# Connectors.net
KiCad netlist of a schematic drawn in Altium Designer
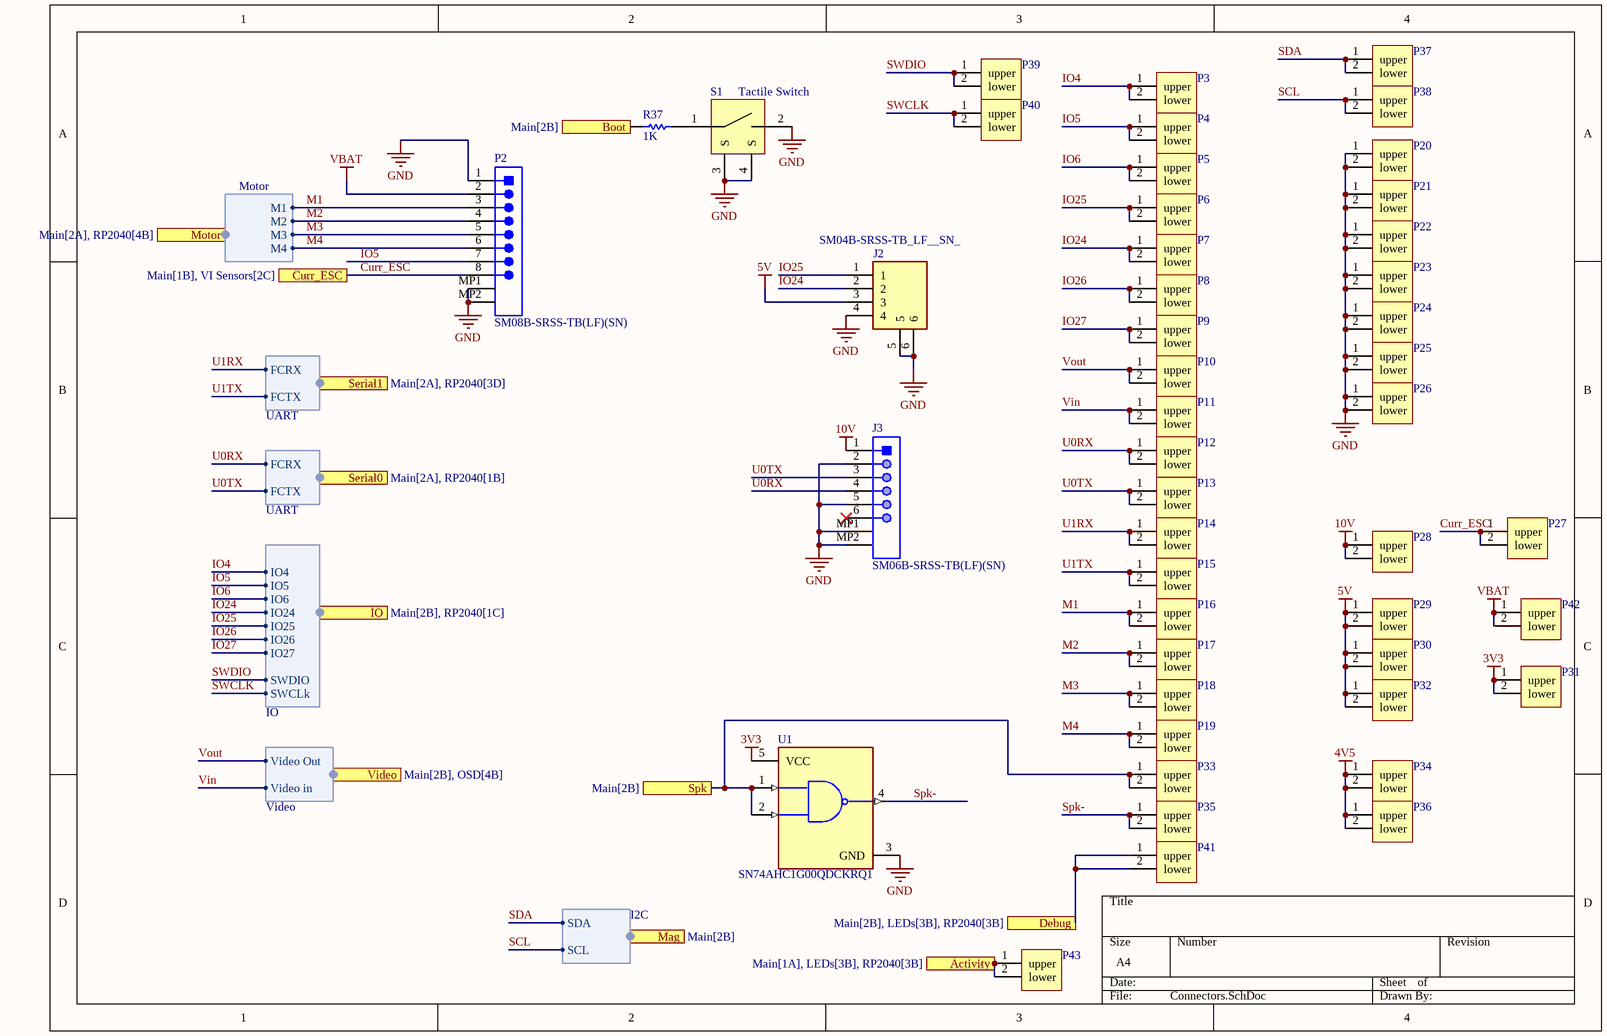
[diagram p0: Connectors.SchDoc]

(export (version "E")
  (design (tool "Eeschema 10.0.6"))
  (components
    (comp (ref "J2")
      (value "SM04B-SRSS-TB_LF__SN_")
      (footprint "SM04B-SRSS-TB(LFSN)")
      (description "Connector")
      (fields (field (name "MANUFACTURER_PART_NUMBER") "SM04B-SRSS-TB(LF)(SN)"))
      (libsource (lib "Custom Components") (part "SM04B-SRSS-TB_LF__SN_"))
    )
    (comp (ref "J3")
      (value "SM06B-SRSS-TB(LF)(SN)")
      (footprint "JST-SM06B-SRSS-TB_V")
      (description "Male Header, Pitch 1 mm, 1 x 6 Position, Height 2.95 mm, -25 to 85 degC, RoHS, Tape and Reel")
      (fields (field (name "MANUFACTURER") "JST"))
      (libsource (lib "Altium Content Vault") (part "CN-1P-2M-R6"))
    )
    (comp (ref "P2")
      (value "SM08B-SRSS-TB(LF)(SN)")
      (footprint "JST-SM08B-SRSS-TB_V")
      (description "Male Header, Pitch 1 mm, 1 x 8 Position, Height 2.95 mm, -25 to 85 degC, RoHS, Tape and Reel")
      (fields (field (name "MANUFACTURER") "JST"))
      (libsource (lib "Altium Content Vault") (part "CN-1P-2M-R8"))
    )
    (comp (ref "P3")
      (value "solder pad rounded double sided")
      (footprint "solder pad double sided rounded - duplicate")
      (libsource (lib "Custom Components") (part "solder pad rounded double sided"))
    )
    (comp (ref "P4")
      (value "solder pad rounded double sided")
      (footprint "solder pad double sided rounded - duplicate")
      (libsource (lib "Custom Components") (part "solder pad rounded double sided"))
    )
    (comp (ref "P5")
      (value "solder pad rounded double sided")
      (footprint "solder pad double sided rounded - duplicate")
      (libsource (lib "Custom Components") (part "solder pad rounded double sided"))
    )
    (comp (ref "P6")
      (value "solder pad rounded double sided")
      (footprint "solder pad double sided rounded - duplicate")
      (libsource (lib "Custom Components") (part "solder pad rounded double sided"))
    )
    (comp (ref "P7")
      (value "solder pad rounded double sided")
      (footprint "solder pad double sided rounded - duplicate")
      (libsource (lib "Custom Components") (part "solder pad rounded double sided"))
    )
    (comp (ref "P8")
      (value "solder pad rounded double sided")
      (footprint "solder pad double sided rounded - duplicate")
      (libsource (lib "Custom Components") (part "solder pad rounded double sided"))
    )
    (comp (ref "P9")
      (value "solder pad rounded double sided")
      (footprint "solder pad double sided rounded - duplicate")
      (libsource (lib "Custom Components") (part "solder pad rounded double sided"))
    )
    (comp (ref "P10")
      (value "solder pad rounded double sided")
      (footprint "solder pad double sided rounded - duplicate")
      (libsource (lib "Custom Components") (part "solder pad rounded double sided"))
    )
    (comp (ref "P11")
      (value "solder pad rounded double sided")
      (footprint "solder pad double sided rounded - duplicate")
      (libsource (lib "Custom Components") (part "solder pad rounded double sided"))
    )
    (comp (ref "P12")
      (value "solder pad rounded double sided")
      (footprint "solder pad double sided rounded - duplicate")
      (libsource (lib "Custom Components") (part "solder pad rounded double sided"))
    )
    (comp (ref "P13")
      (value "solder pad rounded double sided")
      (footprint "solder pad double sided rounded - duplicate")
      (libsource (lib "Custom Components") (part "solder pad rounded double sided"))
    )
    (comp (ref "P14")
      (value "solder pad rounded double sided")
      (footprint "solder pad double sided rounded - duplicate")
      (libsource (lib "Custom Components") (part "solder pad rounded double sided"))
    )
    (comp (ref "P15")
      (value "solder pad rounded double sided")
      (footprint "solder pad double sided rounded - duplicate")
      (libsource (lib "Custom Components") (part "solder pad rounded double sided"))
    )
    (comp (ref "P16")
      (value "solder pad rounded double sided")
      (footprint "solder pad double sided rounded - duplicate")
      (libsource (lib "Custom Components") (part "solder pad rounded double sided"))
    )
    (comp (ref "P17")
      (value "solder pad rounded double sided")
      (footprint "solder pad double sided rounded - duplicate")
      (libsource (lib "Custom Components") (part "solder pad rounded double sided"))
    )
    (comp (ref "P18")
      (value "solder pad rounded double sided")
      (footprint "solder pad double sided rounded - duplicate")
      (libsource (lib "Custom Components") (part "solder pad rounded double sided"))
    )
    (comp (ref "P19")
      (value "solder pad rounded double sided")
      (footprint "solder pad double sided rounded - duplicate")
      (libsource (lib "Custom Components") (part "solder pad rounded double sided"))
    )
    (comp (ref "P20")
      (value "solder pad square double sided")
      (footprint "solder pad double sided square")
      (libsource (lib "Custom Components") (part "solder pad square double sided"))
    )
    (comp (ref "P21")
      (value "solder pad square double sided")
      (footprint "solder pad double sided square")
      (libsource (lib "Custom Components") (part "solder pad square double sided"))
    )
    (comp (ref "P22")
      (value "solder pad square double sided")
      (footprint "solder pad double sided square")
      (libsource (lib "Custom Components") (part "solder pad square double sided"))
    )
    (comp (ref "P23")
      (value "solder pad square double sided")
      (footprint "solder pad double sided square")
      (libsource (lib "Custom Components") (part "solder pad square double sided"))
    )
    (comp (ref "P24")
      (value "solder pad square double sided")
      (footprint "solder pad double sided square")
      (libsource (lib "Custom Components") (part "solder pad square double sided"))
    )
    (comp (ref "P25")
      (value "solder pad square double sided")
      (footprint "solder pad double sided square")
      (libsource (lib "Custom Components") (part "solder pad square double sided"))
    )
    (comp (ref "P26")
      (value "solder pad square double sided")
      (footprint "solder pad double sided square")
      (libsource (lib "Custom Components") (part "solder pad square double sided"))
    )
    (comp (ref "P27")
      (value "solder pad chamfered double sided")
      (footprint "solder pad double sided chamfered")
      (libsource (lib "Custom Components") (part "solder pad chamfered double sided"))
    )
    (comp (ref "P28")
      (value "solder pad chamfered double sided")
      (footprint "solder pad double sided chamfered")
      (libsource (lib "Custom Components") (part "solder pad chamfered double sided"))
    )
    (comp (ref "P29")
      (value "solder pad chamfered double sided")
      (footprint "solder pad double sided chamfered")
      (libsource (lib "Custom Components") (part "solder pad chamfered double sided"))
    )
    (comp (ref "P30")
      (value "solder pad chamfered double sided")
      (footprint "solder pad double sided chamfered")
      (libsource (lib "Custom Components") (part "solder pad chamfered double sided"))
    )
    (comp (ref "P31")
      (value "solder pad chamfered double sided")
      (footprint "solder pad double sided chamfered")
      (libsource (lib "Custom Components") (part "solder pad chamfered double sided"))
    )
    (comp (ref "P32")
      (value "solder pad chamfered double sided")
      (footprint "solder pad double sided chamfered")
      (libsource (lib "Custom Components") (part "solder pad chamfered double sided"))
    )
    (comp (ref "P33")
      (value "solder pad rounded double sided")
      (footprint "solder pad double sided rounded - duplicate")
      (libsource (lib "Custom Components") (part "solder pad rounded double sided"))
    )
    (comp (ref "P34")
      (value "solder pad chamfered double sided")
      (footprint "solder pad double sided chamfered")
      (libsource (lib "Custom Components") (part "solder pad chamfered double sided"))
    )
    (comp (ref "P35")
      (value "solder pad rounded double sided")
      (footprint "solder pad double sided rounded - duplicate")
      (libsource (lib "Custom Components") (part "solder pad rounded double sided"))
    )
    (comp (ref "P36")
      (value "solder pad chamfered double sided")
      (footprint "solder pad double sided chamfered")
      (libsource (lib "Custom Components") (part "solder pad chamfered double sided"))
    )
    (comp (ref "P37")
      (value "solder pad rounded double sided")
      (footprint "solder pad double sided rounded - duplicate")
      (libsource (lib "Custom Components") (part "solder pad rounded double sided"))
    )
    (comp (ref "P38")
      (value "solder pad rounded double sided")
      (footprint "solder pad double sided rounded - duplicate")
      (libsource (lib "Custom Components") (part "solder pad rounded double sided"))
    )
    (comp (ref "P39")
      (value "solder pad rounded double sided")
      (footprint "solder pad double sided rounded - duplicate")
      (libsource (lib "Custom Components") (part "solder pad rounded double sided"))
    )
    (comp (ref "P40")
      (value "solder pad rounded double sided")
      (footprint "solder pad double sided rounded - duplicate")
      (libsource (lib "Custom Components") (part "solder pad rounded double sided"))
    )
    (comp (ref "P41")
      (value "solder pad rounded double sided")
      (footprint "solder pad double sided rounded - duplicate")
      (libsource (lib "Custom Components") (part "solder pad rounded double sided"))
    )
    (comp (ref "P42")
      (value "solder pad chamfered double sided")
      (footprint "solder pad double sided chamfered")
      (libsource (lib "Custom Components") (part "solder pad chamfered double sided"))
    )
    (comp (ref "P43")
      (value "solder pad rounded double sided")
      (footprint "solder pad double sided rounded - duplicate")
      (libsource (lib "Custom Components") (part "solder pad rounded double sided"))
    )
    (comp (ref "R37")
      (value "1K")
      (footprint "RESC0603(1608)_N")
      (description "Chipwiderstand, SMD, Baureihe MC, 1%")
      (fields (field (name "MANUFACTURER") "Multicomp"))
      (libsource (lib "Standardbauteile") (part "Res 1K"))
    )
    (comp (ref "S1")
      (value "Tactile Switch")
      (footprint "Tactile Switch")
      (libsource (lib "Custom Components") (part "Tactile Switch"))
    )
    (comp (ref "U1")
      (value "SN74AHC1G00QDCKRQ1")
      (footprint "FP-DCK0005A-IPC_A")
      (description "IC GATE NAND 1CH 2-INP SC70-5")
      (libsource (lib "Altium Content Vault") (part "4a1d673274a90161e31fa41c5f74738"))
    )
  )
  (nets
    (net (code "6") (name "/Activity") (class "Default")
      (node (ref "P43") (pin "1") (pinfunction "upper_1") (pintype "passive"))
      (node (ref "P43") (pin "2") (pinfunction "lower_2") (pintype "passive"))
    )
    (net (code "7") (name "/Boot") (class "Default")
      (node (ref "R37") (pin "1") (pinfunction "1_1") (pintype "passive"))
    )
    (net (code "8") (name "/Curr_ESC") (class "Default")
      (node (ref "P2") (pin "8") (pinfunction "8_8") (pintype "passive"))
      (node (ref "P27") (pin "1") (pinfunction "upper_1") (pintype "passive"))
      (node (ref "P27") (pin "2") (pinfunction "lower_2") (pintype "passive"))
    )
    (net (code "9") (name "/Debug") (class "Default")
      (node (ref "P41") (pin "1") (pinfunction "upper_1") (pintype "passive"))
      (node (ref "P41") (pin "2") (pinfunction "lower_2") (pintype "passive"))
    )
    (net (code "10") (name "/IO4") (class "Default")
      (node (ref "P3") (pin "1") (pinfunction "upper_1") (pintype "passive"))
      (node (ref "P3") (pin "2") (pinfunction "lower_2") (pintype "passive"))
    )
    (net (code "11") (name "/IO5") (class "Default")
      (node (ref "P2") (pin "7") (pinfunction "7_7") (pintype "passive"))
      (node (ref "P4") (pin "1") (pinfunction "upper_1") (pintype "passive"))
      (node (ref "P4") (pin "2") (pinfunction "lower_2") (pintype "passive"))
    )
    (net (code "12") (name "/IO6") (class "Default")
      (node (ref "P5") (pin "1") (pinfunction "upper_1") (pintype "passive"))
      (node (ref "P5") (pin "2") (pinfunction "lower_2") (pintype "passive"))
    )
    (net (code "13") (name "/IO24") (class "Default")
      (node (ref "J2") (pin "2") (pinfunction "2_2") (pintype "passive"))
      (node (ref "P7") (pin "1") (pinfunction "upper_1") (pintype "passive"))
      (node (ref "P7") (pin "2") (pinfunction "lower_2") (pintype "passive"))
    )
    (net (code "14") (name "/IO25") (class "Default")
      (node (ref "J2") (pin "1") (pinfunction "1_1") (pintype "passive"))
      (node (ref "P6") (pin "1") (pinfunction "upper_1") (pintype "passive"))
      (node (ref "P6") (pin "2") (pinfunction "lower_2") (pintype "passive"))
    )
    (net (code "15") (name "/IO26") (class "Default")
      (node (ref "P8") (pin "1") (pinfunction "upper_1") (pintype "passive"))
      (node (ref "P8") (pin "2") (pinfunction "lower_2") (pintype "passive"))
    )
    (net (code "16") (name "/IO27") (class "Default")
      (node (ref "P9") (pin "1") (pinfunction "upper_1") (pintype "passive"))
      (node (ref "P9") (pin "2") (pinfunction "lower_2") (pintype "passive"))
    )
    (net (code "17") (name "/M1") (class "Default")
      (node (ref "P16") (pin "1") (pinfunction "upper_1") (pintype "passive"))
      (node (ref "P16") (pin "2") (pinfunction "lower_2") (pintype "passive"))
      (node (ref "P2") (pin "3") (pinfunction "3_3") (pintype "passive"))
    )
    (net (code "18") (name "/M2") (class "Default")
      (node (ref "P17") (pin "1") (pinfunction "upper_1") (pintype "passive"))
      (node (ref "P17") (pin "2") (pinfunction "lower_2") (pintype "passive"))
      (node (ref "P2") (pin "4") (pinfunction "4_4") (pintype "passive"))
    )
    (net (code "19") (name "/M3") (class "Default")
      (node (ref "P18") (pin "1") (pinfunction "upper_1") (pintype "passive"))
      (node (ref "P18") (pin "2") (pinfunction "lower_2") (pintype "passive"))
      (node (ref "P2") (pin "5") (pinfunction "5_5") (pintype "passive"))
    )
    (net (code "20") (name "/M4") (class "Default")
      (node (ref "P19") (pin "1") (pinfunction "upper_1") (pintype "passive"))
      (node (ref "P19") (pin "2") (pinfunction "lower_2") (pintype "passive"))
      (node (ref "P2") (pin "6") (pinfunction "6_6") (pintype "passive"))
    )
    (net (code "21") (name "/SCL") (class "Default")
      (node (ref "P38") (pin "1") (pinfunction "upper_1") (pintype "passive"))
      (node (ref "P38") (pin "2") (pinfunction "lower_2") (pintype "passive"))
    )
    (net (code "22") (name "/SDA") (class "Default")
      (node (ref "P37") (pin "1") (pinfunction "upper_1") (pintype "passive"))
      (node (ref "P37") (pin "2") (pinfunction "lower_2") (pintype "passive"))
    )
    (net (code "23") (name "/SWCLK") (class "Default")
      (node (ref "P40") (pin "1") (pinfunction "upper_1") (pintype "passive"))
      (node (ref "P40") (pin "2") (pinfunction "lower_2") (pintype "passive"))
    )
    (net (code "24") (name "/SWDIO") (class "Default")
      (node (ref "P39") (pin "1") (pinfunction "upper_1") (pintype "passive"))
      (node (ref "P39") (pin "2") (pinfunction "lower_2") (pintype "passive"))
    )
    (net (code "25") (name "/Spk") (class "Default")
      (node (ref "P33") (pin "1") (pinfunction "upper_1") (pintype "passive"))
      (node (ref "P33") (pin "2") (pinfunction "lower_2") (pintype "passive"))
      (node (ref "U1") (pin "1") (pinfunction "A_1") (pintype "input"))
      (node (ref "U1") (pin "2") (pinfunction "B_2") (pintype "input"))
    )
    (net (code "26") (name "/Spk-") (class "Default")
      (node (ref "P35") (pin "1") (pinfunction "upper_1") (pintype "passive"))
      (node (ref "P35") (pin "2") (pinfunction "lower_2") (pintype "passive"))
      (node (ref "U1") (pin "4") (pinfunction "Y_4") (pintype "output"))
    )
    (net (code "27") (name "/U0RX") (class "Default")
      (node (ref "J3") (pin "4") (pinfunction "4_4") (pintype "passive"))
      (node (ref "P12") (pin "1") (pinfunction "upper_1") (pintype "passive"))
      (node (ref "P12") (pin "2") (pinfunction "lower_2") (pintype "passive"))
    )
    (net (code "28") (name "/U0TX") (class "Default")
      (node (ref "J3") (pin "3") (pinfunction "3_3") (pintype "passive"))
      (node (ref "P13") (pin "1") (pinfunction "upper_1") (pintype "passive"))
      (node (ref "P13") (pin "2") (pinfunction "lower_2") (pintype "passive"))
    )
    (net (code "29") (name "/U1RX") (class "Default")
      (node (ref "P14") (pin "1") (pinfunction "upper_1") (pintype "passive"))
      (node (ref "P14") (pin "2") (pinfunction "lower_2") (pintype "passive"))
    )
    (net (code "30") (name "/U1TX") (class "Default")
      (node (ref "P15") (pin "1") (pinfunction "upper_1") (pintype "passive"))
      (node (ref "P15") (pin "2") (pinfunction "lower_2") (pintype "passive"))
    )
    (net (code "31") (name "/Vin") (class "Default")
      (node (ref "P11") (pin "1") (pinfunction "upper_1") (pintype "passive"))
      (node (ref "P11") (pin "2") (pinfunction "lower_2") (pintype "passive"))
    )
    (net (code "32") (name "/Vout") (class "Default")
      (node (ref "P10") (pin "1") (pinfunction "upper_1") (pintype "passive"))
      (node (ref "P10") (pin "2") (pinfunction "lower_2") (pintype "passive"))
    )
    (net (code "38") (name "3V3") (class "Default")
      (node (ref "P31") (pin "1") (pinfunction "upper_1") (pintype "passive"))
      (node (ref "P31") (pin "2") (pinfunction "lower_2") (pintype "passive"))
      (node (ref "U1") (pin "5") (pinfunction "VCC_5") (pintype "power_in"))
    )
    (net (code "39") (name "4V5") (class "Default")
      (node (ref "P34") (pin "1") (pinfunction "upper_1") (pintype "passive"))
      (node (ref "P34") (pin "2") (pinfunction "lower_2") (pintype "passive"))
      (node (ref "P36") (pin "1") (pinfunction "upper_1") (pintype "passive"))
      (node (ref "P36") (pin "2") (pinfunction "lower_2") (pintype "passive"))
    )
    (net (code "40") (name "5V") (class "Default")
      (node (ref "J2") (pin "3") (pinfunction "3_3") (pintype "passive"))
      (node (ref "P29") (pin "1") (pinfunction "upper_1") (pintype "passive"))
      (node (ref "P29") (pin "2") (pinfunction "lower_2") (pintype "passive"))
      (node (ref "P30") (pin "1") (pinfunction "upper_1") (pintype "passive"))
      (node (ref "P30") (pin "2") (pinfunction "lower_2") (pintype "passive"))
      (node (ref "P32") (pin "1") (pinfunction "upper_1") (pintype "passive"))
      (node (ref "P32") (pin "2") (pinfunction "lower_2") (pintype "passive"))
    )
    (net (code "41") (name "10V") (class "Default")
      (node (ref "J3") (pin "1") (pinfunction "1_1") (pintype "passive"))
      (node (ref "P28") (pin "1") (pinfunction "upper_1") (pintype "passive"))
      (node (ref "P28") (pin "2") (pinfunction "lower_2") (pintype "passive"))
    )
    (net (code "42") (name "GND") (class "Default")
      (node (ref "J2") (pin "4") (pinfunction "4_4") (pintype "passive"))
      (node (ref "J2") (pin "5") (pinfunction "5_5") (pintype "passive"))
      (node (ref "J2") (pin "6") (pinfunction "6_6") (pintype "passive"))
      (node (ref "J3") (pin "2") (pinfunction "2_2") (pintype "passive"))
      (node (ref "J3") (pin "5") (pinfunction "5_5") (pintype "passive"))
      (node (ref "J3") (pin "MP1") (pinfunction "MP1_MP1") (pintype "passive"))
      (node (ref "J3") (pin "MP2") (pinfunction "MP2_MP2") (pintype "passive"))
      (node (ref "P2") (pin "1") (pinfunction "1_1") (pintype "passive"))
      (node (ref "P2") (pin "MP1") (pinfunction "MP1_MP1") (pintype "passive"))
      (node (ref "P2") (pin "MP2") (pinfunction "MP2_MP2") (pintype "passive"))
      (node (ref "P20") (pin "1") (pinfunction "upper_1") (pintype "passive"))
      (node (ref "P20") (pin "2") (pinfunction "lower_2") (pintype "passive"))
      (node (ref "P21") (pin "1") (pinfunction "upper_1") (pintype "passive"))
      (node (ref "P21") (pin "2") (pinfunction "lower_2") (pintype "passive"))
      (node (ref "P22") (pin "1") (pinfunction "upper_1") (pintype "passive"))
      (node (ref "P22") (pin "2") (pinfunction "lower_2") (pintype "passive"))
      (node (ref "P23") (pin "1") (pinfunction "upper_1") (pintype "passive"))
      (node (ref "P23") (pin "2") (pinfunction "lower_2") (pintype "passive"))
      (node (ref "P24") (pin "1") (pinfunction "upper_1") (pintype "passive"))
      (node (ref "P24") (pin "2") (pinfunction "lower_2") (pintype "passive"))
      (node (ref "P25") (pin "1") (pinfunction "upper_1") (pintype "passive"))
      (node (ref "P25") (pin "2") (pinfunction "lower_2") (pintype "passive"))
      (node (ref "P26") (pin "1") (pinfunction "upper_1") (pintype "passive"))
      (node (ref "P26") (pin "2") (pinfunction "lower_2") (pintype "passive"))
      (node (ref "S1") (pin "2") (pintype "passive"))
      (node (ref "S1") (pin "3") (pinfunction "S_3") (pintype "passive"))
      (node (ref "S1") (pin "4") (pinfunction "S_4") (pintype "passive"))
      (node (ref "U1") (pin "3") (pinfunction "GND_3") (pintype "power_in"))
    )
    (net (code "43") (name "Net-(R37-Pad2)") (class "Default")
      (node (ref "R37") (pin "2") (pinfunction "2_2") (pintype "passive"))
      (node (ref "S1") (pin "1") (pintype "passive"))
    )
    (net (code "44") (name "VBAT") (class "Default")
      (node (ref "P2") (pin "2") (pinfunction "2_2") (pintype "passive"))
      (node (ref "P42") (pin "1") (pinfunction "upper_1") (pintype "passive"))
      (node (ref "P42") (pin "2") (pinfunction "lower_2") (pintype "passive"))
    )
    (net (code "45") (name "unconnected-(J3-Pad6)") (class "Default")
      (node (ref "J3") (pin "6") (pinfunction "6_6") (pintype "passive+no_connect"))
    )
  )
)
